# Motor_Speed_Controller.net
KiCad netlist of a schematic drawn in EAGLE
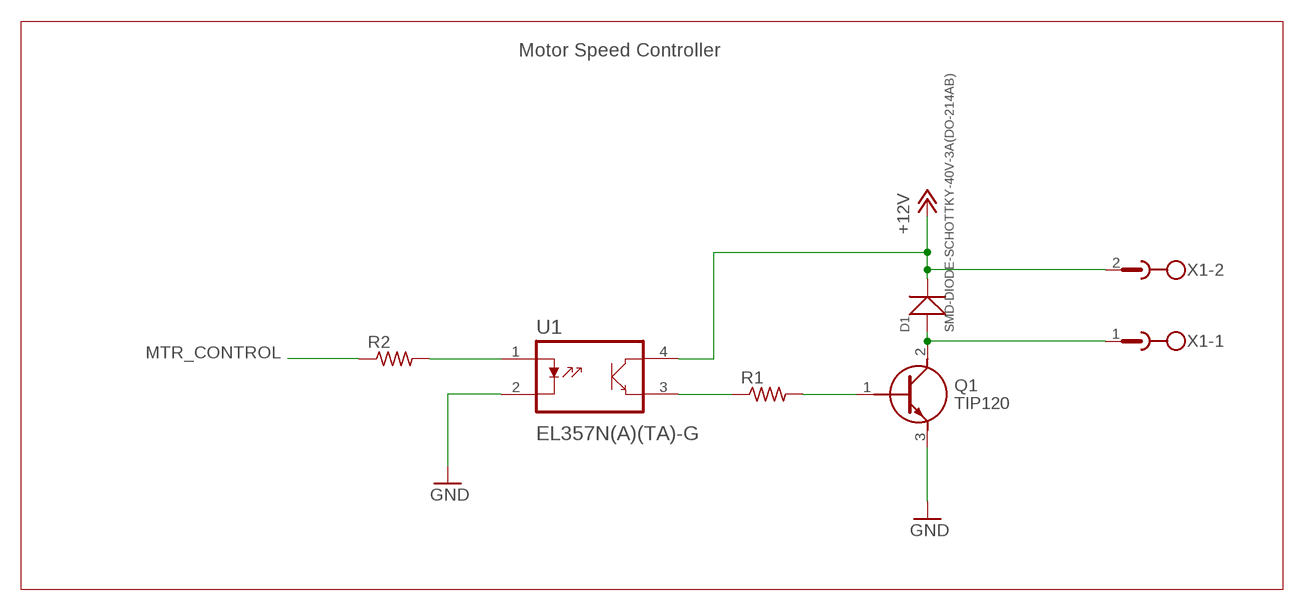
[diagram p0: schematic, sheet 1]

(export (version "E")
  (design (tool "Eeschema 10.0.6"))
  (components
    (comp (ref "D1")
      (value "SMD-DIODE-SCHOTTKY-40V-3A(DO-214AB)")
      (footprint "eagle-import:DO-214AB")
      (fields (field (name "MF") "Vishay") (field (name "MP") "SS34-E3/57T"))
      (libsource (lib "eagle-import") (part "SMD-DIODE-SCHOTTKY-40V-3A(DO-214AB)"))
    )
    (comp (ref "Q1")
      (value "TIP120")
      (footprint "eagle-import:TO220")
      (fields (field (name "MOUSER_PART_NUMBER") "512-TIP120"))
      (libsource (lib "eagle-import") (part "TIP120"))
    )
    (comp (ref "R1")
      (value "R-US_R0805")
      (footprint "eagle-import:R0805")
      (libsource (lib "eagle-import") (part "R-US_R0805"))
    )
    (comp (ref "R2")
      (value "R-US_R0805")
      (footprint "eagle-import:R0805")
      (libsource (lib "eagle-import") (part "R-US_R0805"))
    )
    (comp (ref "U1")
      (value "EL357N(A)(TA)-G")
      (footprint "eagle-import:SOP254P700X200-4N")
      (fields (field (name "MF") "Everlight") (field (name "MP") "EL357N_A__TA_-G"))
      (libsource (lib "eagle-import") (part "EL357N(A)(TA)-G"))
    )
    (comp (ref "X1")
      (value "MSTBA4")
      (footprint "eagle-import:MSTBA4")
      (fields (field (name "MF") "FARNELL") (field (name "MPN") "1757268"))
      (libsource (lib "eagle-import") (part "MSTBA4"))
    )
  )
  (nets
    (net (code "1") (name "+12V") (class "Default")
      (node (ref "D1") (pin "2") (pinfunction "-_2") (pintype "passive"))
      (node (ref "U1") (pin "4") (pinfunction "C_4") (pintype "passive"))
      (node (ref "X1") (pin "2") (pinfunction "1_2") (pintype "passive"))
    )
    (net (code "2") (name "/MTR_CONTROL") (class "Default")
      (node (ref "R2") (pin "1") (pinfunction "1_1") (pintype "passive"))
    )
    (net (code "3") (name "GND") (class "Default")
      (node (ref "Q1") (pin "3") (pinfunction "E_3") (pintype "bidirectional"))
      (node (ref "U1") (pin "2") (pinfunction "K_2") (pintype "passive"))
    )
    (net (code "4") (name "Net-(D1-+)") (class "Default")
      (node (ref "D1") (pin "1") (pinfunction "+_1") (pintype "passive"))
      (node (ref "Q1") (pin "2") (pinfunction "C_2") (pintype "bidirectional"))
      (node (ref "X1") (pin "1") (pinfunction "1_1") (pintype "passive"))
    )
    (net (code "5") (name "Net-(Q1-B)") (class "Default")
      (node (ref "Q1") (pin "1") (pinfunction "B_1") (pintype "bidirectional"))
      (node (ref "R1") (pin "2") (pinfunction "2_2") (pintype "passive"))
    )
    (net (code "6") (name "Net-(U1-A)") (class "Default")
      (node (ref "R2") (pin "2") (pinfunction "2_2") (pintype "passive"))
      (node (ref "U1") (pin "1") (pinfunction "A_1") (pintype "passive"))
    )
    (net (code "7") (name "Net-(U1-E)") (class "Default")
      (node (ref "R1") (pin "1") (pinfunction "1_1") (pintype "passive"))
      (node (ref "U1") (pin "3") (pinfunction "E_3") (pintype "passive"))
    )
  )
)
